# BIT_6.net
KiCad netlist of a schematic drawn in EasyEDA
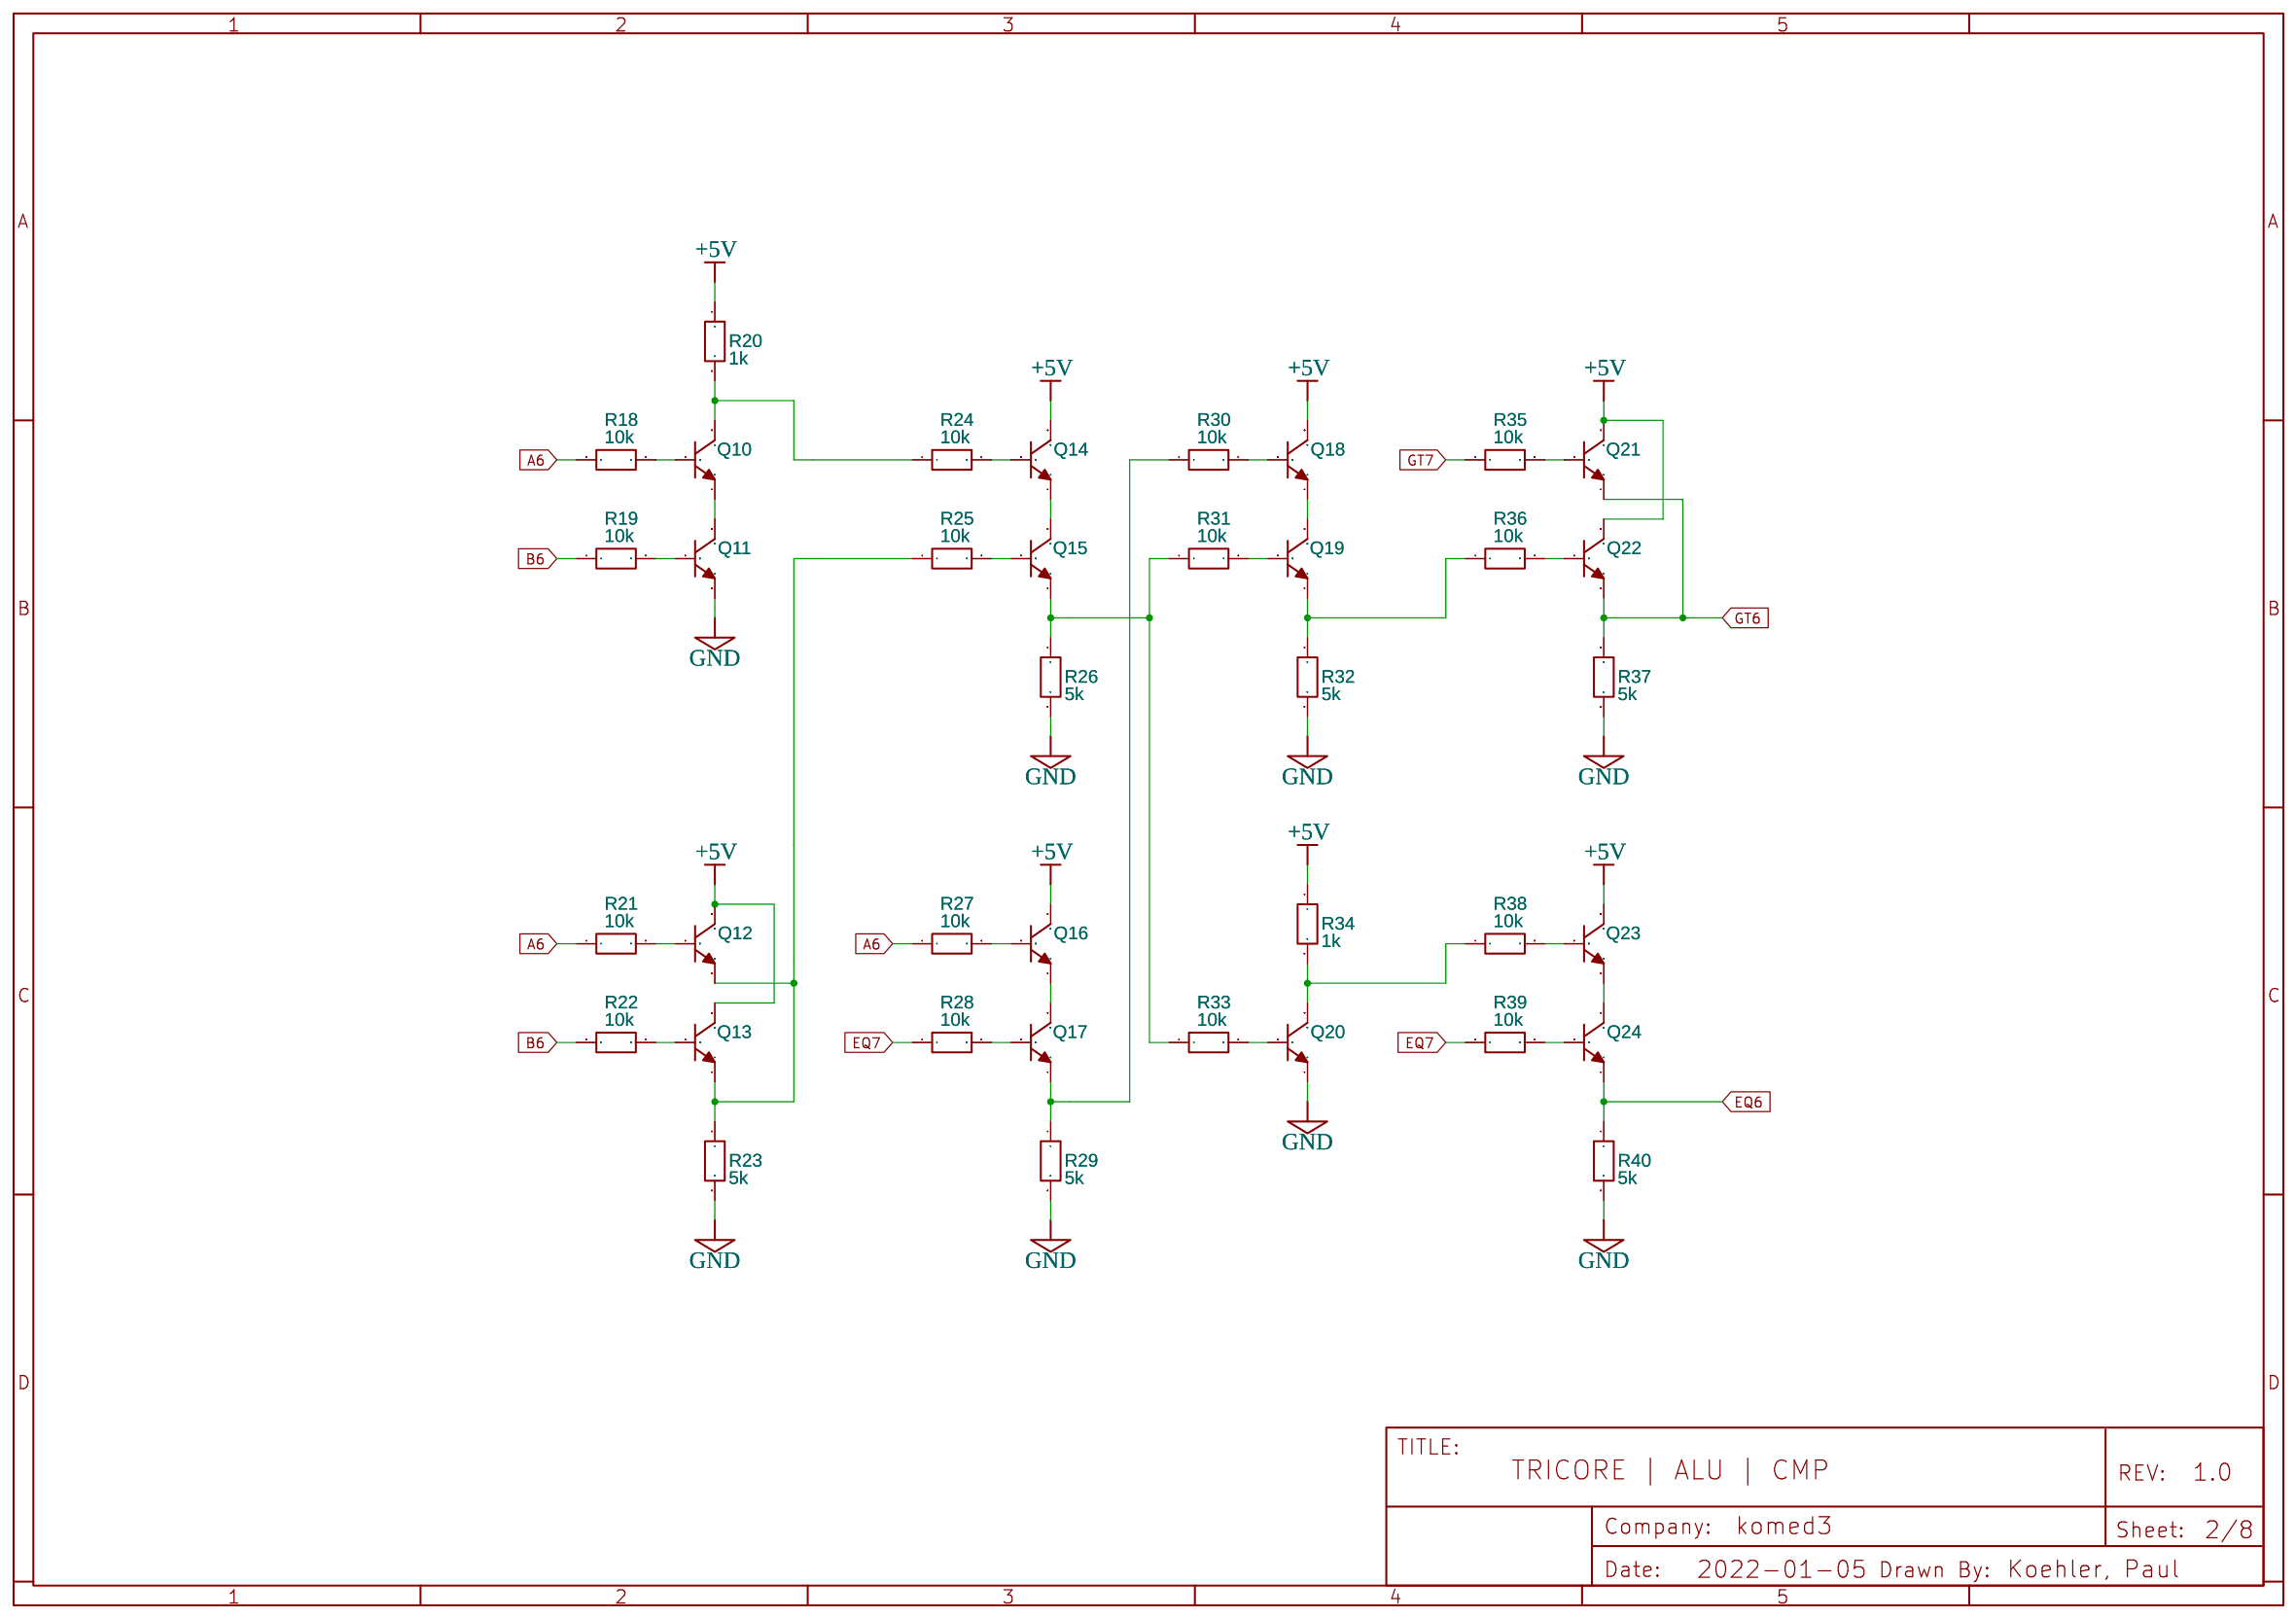
[diagram p0: schematic sheet]

(export (version "E")
  (design (tool "Eeschema 10.0.6"))
  (components
    (comp (ref "Q10")
      (value "2N3904(TO-92)")
      (fields (field (name "BOM_Manufacturer Part") "2N3904") (field (name "BOM_Supplier Part") "C118538"))
      (libsource (lib "") (part "2N3904(TO-92)"))
    )
    (comp (ref "Q11")
      (value "2N3904(TO-92)")
      (fields (field (name "BOM_Manufacturer Part") "2N3904") (field (name "BOM_Supplier Part") "C118538"))
      (libsource (lib "") (part "2N3904(TO-92)"))
    )
    (comp (ref "Q12")
      (value "2N3904(TO-92)")
      (fields (field (name "BOM_Manufacturer Part") "2N3904") (field (name "BOM_Supplier Part") "C118538"))
      (libsource (lib "") (part "2N3904(TO-92)"))
    )
    (comp (ref "Q13")
      (value "2N3904(TO-92)")
      (fields (field (name "BOM_Manufacturer Part") "2N3904") (field (name "BOM_Supplier Part") "C118538"))
      (libsource (lib "") (part "2N3904(TO-92)"))
    )
    (comp (ref "Q14")
      (value "2N3904(TO-92)")
      (fields (field (name "BOM_Manufacturer Part") "2N3904") (field (name "BOM_Supplier Part") "C118538"))
      (libsource (lib "") (part "2N3904(TO-92)"))
    )
    (comp (ref "Q15")
      (value "2N3904(TO-92)")
      (fields (field (name "BOM_Manufacturer Part") "2N3904") (field (name "BOM_Supplier Part") "C118538"))
      (libsource (lib "") (part "2N3904(TO-92)"))
    )
    (comp (ref "Q16")
      (value "2N3904(TO-92)")
      (fields (field (name "BOM_Manufacturer Part") "2N3904") (field (name "BOM_Supplier Part") "C118538"))
      (libsource (lib "") (part "2N3904(TO-92)"))
    )
    (comp (ref "Q17")
      (value "2N3904(TO-92)")
      (fields (field (name "BOM_Manufacturer Part") "2N3904") (field (name "BOM_Supplier Part") "C118538"))
      (libsource (lib "") (part "2N3904(TO-92)"))
    )
    (comp (ref "Q18")
      (value "2N3904(TO-92)")
      (fields (field (name "BOM_Manufacturer Part") "2N3904") (field (name "BOM_Supplier Part") "C118538"))
      (libsource (lib "") (part "2N3904(TO-92)"))
    )
    (comp (ref "Q19")
      (value "2N3904(TO-92)")
      (fields (field (name "BOM_Manufacturer Part") "2N3904") (field (name "BOM_Supplier Part") "C118538"))
      (libsource (lib "") (part "2N3904(TO-92)"))
    )
    (comp (ref "Q20")
      (value "2N3904(TO-92)")
      (fields (field (name "BOM_Manufacturer Part") "2N3904") (field (name "BOM_Supplier Part") "C118538"))
      (libsource (lib "") (part "2N3904(TO-92)"))
    )
    (comp (ref "Q21")
      (value "2N3904(TO-92)")
      (fields (field (name "BOM_Manufacturer Part") "2N3904") (field (name "BOM_Supplier Part") "C118538"))
      (libsource (lib "") (part "2N3904(TO-92)"))
    )
    (comp (ref "Q22")
      (value "2N3904(TO-92)")
      (fields (field (name "BOM_Manufacturer Part") "2N3904") (field (name "BOM_Supplier Part") "C118538"))
      (libsource (lib "") (part "2N3904(TO-92)"))
    )
    (comp (ref "Q23")
      (value "2N3904(TO-92)")
      (fields (field (name "BOM_Manufacturer Part") "2N3904") (field (name "BOM_Supplier Part") "C118538"))
      (libsource (lib "") (part "2N3904(TO-92)"))
    )
    (comp (ref "Q24")
      (value "2N3904(TO-92)")
      (fields (field (name "BOM_Manufacturer Part") "2N3904") (field (name "BOM_Supplier Part") "C118538"))
      (libsource (lib "") (part "2N3904(TO-92)"))
    )
    (comp (ref "R18") (value "10k") (libsource (lib "") (part "R_AXIAL-0.3_EU")))
    (comp (ref "R19") (value "10k") (libsource (lib "") (part "R_AXIAL-0.3_EU")))
    (comp (ref "R20") (value "1k") (libsource (lib "") (part "R_AXIAL-0.3_EU_1")))
    (comp (ref "R21") (value "10k") (libsource (lib "") (part "R_AXIAL-0.3_EU")))
    (comp (ref "R22") (value "10k") (libsource (lib "") (part "R_AXIAL-0.3_EU")))
    (comp (ref "R23") (value "5k") (libsource (lib "") (part "R_AXIAL-0.3_EU_1")))
    (comp (ref "R24") (value "10k") (libsource (lib "") (part "R_AXIAL-0.3_EU")))
    (comp (ref "R25") (value "10k") (libsource (lib "") (part "R_AXIAL-0.3_EU")))
    (comp (ref "R26") (value "5k") (libsource (lib "") (part "R_AXIAL-0.3_EU_1")))
    (comp (ref "R27") (value "10k") (libsource (lib "") (part "R_AXIAL-0.3_EU")))
    (comp (ref "R28") (value "10k") (libsource (lib "") (part "R_AXIAL-0.3_EU")))
    (comp (ref "R29") (value "5k") (libsource (lib "") (part "R_AXIAL-0.3_EU_1")))
    (comp (ref "R30") (value "10k") (libsource (lib "") (part "R_AXIAL-0.3_EU")))
    (comp (ref "R31") (value "10k") (libsource (lib "") (part "R_AXIAL-0.3_EU")))
    (comp (ref "R32") (value "5k") (libsource (lib "") (part "R_AXIAL-0.3_EU_1")))
    (comp (ref "R33") (value "10k") (libsource (lib "") (part "R_AXIAL-0.3_EU")))
    (comp (ref "R34") (value "1k") (libsource (lib "") (part "R_AXIAL-0.3_EU_1")))
    (comp (ref "R35") (value "10k") (libsource (lib "") (part "R_AXIAL-0.3_EU")))
    (comp (ref "R36") (value "10k") (libsource (lib "") (part "R_AXIAL-0.3_EU")))
    (comp (ref "R37") (value "5k") (libsource (lib "") (part "R_AXIAL-0.3_EU_1")))
    (comp (ref "R38") (value "10k") (libsource (lib "") (part "R_AXIAL-0.3_EU")))
    (comp (ref "R39") (value "10k") (libsource (lib "") (part "R_AXIAL-0.3_EU")))
    (comp (ref "R40") (value "5k") (libsource (lib "") (part "R_AXIAL-0.3_EU_1")))
  )
  (nets
    (net (code "1") (name "+5V") (class "Default")
      (node (ref "Q12") (pin "3") (pinfunction "C_3") (pintype "unspecified"))
      (node (ref "Q13") (pin "3") (pinfunction "C_3") (pintype "unspecified"))
      (node (ref "Q14") (pin "3") (pinfunction "C_3") (pintype "unspecified"))
      (node (ref "Q16") (pin "3") (pinfunction "C_3") (pintype "unspecified"))
      (node (ref "Q18") (pin "3") (pinfunction "C_3") (pintype "unspecified"))
      (node (ref "Q21") (pin "3") (pinfunction "C_3") (pintype "unspecified"))
      (node (ref "Q22") (pin "3") (pinfunction "C_3") (pintype "unspecified"))
      (node (ref "Q23") (pin "3") (pinfunction "C_3") (pintype "unspecified"))
      (node (ref "R20") (pin "1") (pinfunction "1_1") (pintype "unspecified"))
      (node (ref "R34") (pin "1") (pinfunction "1_1") (pintype "unspecified"))
    )
    (net (code "2") (name "A6") (class "Default")
      (node (ref "R18") (pin "1") (pinfunction "1_1") (pintype "unspecified"))
      (node (ref "R21") (pin "1") (pinfunction "1_1") (pintype "unspecified"))
      (node (ref "R27") (pin "1") (pinfunction "1_1") (pintype "unspecified"))
    )
    (net (code "3") (name "B6") (class "Default")
      (node (ref "R19") (pin "1") (pinfunction "1_1") (pintype "unspecified"))
      (node (ref "R22") (pin "1") (pinfunction "1_1") (pintype "unspecified"))
    )
    (net (code "4") (name "EQ6") (class "Default")
      (node (ref "Q24") (pin "1") (pinfunction "E_1") (pintype "unspecified"))
      (node (ref "R40") (pin "1") (pinfunction "1_1") (pintype "unspecified"))
    )
    (net (code "5") (name "EQ7") (class "Default")
      (node (ref "R28") (pin "1") (pinfunction "1_1") (pintype "unspecified"))
      (node (ref "R39") (pin "1") (pinfunction "1_1") (pintype "unspecified"))
    )
    (net (code "6") (name "GND") (class "Default")
      (node (ref "Q11") (pin "1") (pinfunction "E_1") (pintype "unspecified"))
      (node (ref "Q20") (pin "1") (pinfunction "E_1") (pintype "unspecified"))
      (node (ref "R23") (pin "2") (pinfunction "2_2") (pintype "unspecified"))
      (node (ref "R26") (pin "2") (pinfunction "2_2") (pintype "unspecified"))
      (node (ref "R29") (pin "2") (pinfunction "2_2") (pintype "unspecified"))
      (node (ref "R32") (pin "2") (pinfunction "2_2") (pintype "unspecified"))
      (node (ref "R37") (pin "2") (pinfunction "2_2") (pintype "unspecified"))
      (node (ref "R40") (pin "2") (pinfunction "2_2") (pintype "unspecified"))
    )
    (net (code "7") (name "GT6") (class "Default")
      (node (ref "Q21") (pin "1") (pinfunction "E_1") (pintype "unspecified"))
      (node (ref "Q22") (pin "1") (pinfunction "E_1") (pintype "unspecified"))
      (node (ref "R37") (pin "1") (pinfunction "1_1") (pintype "unspecified"))
    )
    (net (code "8") (name "GT7") (class "Default")
      (node (ref "R35") (pin "1") (pinfunction "1_1") (pintype "unspecified"))
    )
    (net (code "9") (name "Net-(Q10-B)") (class "Default")
      (node (ref "Q10") (pin "2") (pinfunction "B_2") (pintype "unspecified"))
      (node (ref "R18") (pin "2") (pinfunction "2_2") (pintype "unspecified"))
    )
    (net (code "10") (name "Net-(Q10-C)") (class "Default")
      (node (ref "Q10") (pin "3") (pinfunction "C_3") (pintype "unspecified"))
      (node (ref "R20") (pin "2") (pinfunction "2_2") (pintype "unspecified"))
      (node (ref "R24") (pin "1") (pinfunction "1_1") (pintype "unspecified"))
    )
    (net (code "11") (name "Net-(Q10-E)") (class "Default")
      (node (ref "Q10") (pin "1") (pinfunction "E_1") (pintype "unspecified"))
      (node (ref "Q11") (pin "3") (pinfunction "C_3") (pintype "unspecified"))
    )
    (net (code "12") (name "Net-(Q11-B)") (class "Default")
      (node (ref "Q11") (pin "2") (pinfunction "B_2") (pintype "unspecified"))
      (node (ref "R19") (pin "2") (pinfunction "2_2") (pintype "unspecified"))
    )
    (net (code "13") (name "Net-(Q12-B)") (class "Default")
      (node (ref "Q12") (pin "2") (pinfunction "B_2") (pintype "unspecified"))
      (node (ref "R21") (pin "2") (pinfunction "2_2") (pintype "unspecified"))
    )
    (net (code "14") (name "Net-(Q12-E)") (class "Default")
      (node (ref "Q12") (pin "1") (pinfunction "E_1") (pintype "unspecified"))
      (node (ref "Q13") (pin "1") (pinfunction "E_1") (pintype "unspecified"))
      (node (ref "R23") (pin "1") (pinfunction "1_1") (pintype "unspecified"))
      (node (ref "R25") (pin "1") (pinfunction "1_1") (pintype "unspecified"))
    )
    (net (code "15") (name "Net-(Q13-B)") (class "Default")
      (node (ref "Q13") (pin "2") (pinfunction "B_2") (pintype "unspecified"))
      (node (ref "R22") (pin "2") (pinfunction "2_2") (pintype "unspecified"))
    )
    (net (code "16") (name "Net-(Q14-B)") (class "Default")
      (node (ref "Q14") (pin "2") (pinfunction "B_2") (pintype "unspecified"))
      (node (ref "R24") (pin "2") (pinfunction "2_2") (pintype "unspecified"))
    )
    (net (code "17") (name "Net-(Q14-E)") (class "Default")
      (node (ref "Q14") (pin "1") (pinfunction "E_1") (pintype "unspecified"))
      (node (ref "Q15") (pin "3") (pinfunction "C_3") (pintype "unspecified"))
    )
    (net (code "18") (name "Net-(Q15-B)") (class "Default")
      (node (ref "Q15") (pin "2") (pinfunction "B_2") (pintype "unspecified"))
      (node (ref "R25") (pin "2") (pinfunction "2_2") (pintype "unspecified"))
    )
    (net (code "19") (name "Net-(Q15-E)") (class "Default")
      (node (ref "Q15") (pin "1") (pinfunction "E_1") (pintype "unspecified"))
      (node (ref "R26") (pin "1") (pinfunction "1_1") (pintype "unspecified"))
      (node (ref "R31") (pin "1") (pinfunction "1_1") (pintype "unspecified"))
      (node (ref "R33") (pin "1") (pinfunction "1_1") (pintype "unspecified"))
    )
    (net (code "20") (name "Net-(Q16-B)") (class "Default")
      (node (ref "Q16") (pin "2") (pinfunction "B_2") (pintype "unspecified"))
      (node (ref "R27") (pin "2") (pinfunction "2_2") (pintype "unspecified"))
    )
    (net (code "21") (name "Net-(Q16-E)") (class "Default")
      (node (ref "Q16") (pin "1") (pinfunction "E_1") (pintype "unspecified"))
      (node (ref "Q17") (pin "3") (pinfunction "C_3") (pintype "unspecified"))
    )
    (net (code "22") (name "Net-(Q17-B)") (class "Default")
      (node (ref "Q17") (pin "2") (pinfunction "B_2") (pintype "unspecified"))
      (node (ref "R28") (pin "2") (pinfunction "2_2") (pintype "unspecified"))
    )
    (net (code "23") (name "Net-(Q17-E)") (class "Default")
      (node (ref "Q17") (pin "1") (pinfunction "E_1") (pintype "unspecified"))
      (node (ref "R29") (pin "1") (pinfunction "1_1") (pintype "unspecified"))
      (node (ref "R30") (pin "1") (pinfunction "1_1") (pintype "unspecified"))
    )
    (net (code "24") (name "Net-(Q18-B)") (class "Default")
      (node (ref "Q18") (pin "2") (pinfunction "B_2") (pintype "unspecified"))
      (node (ref "R30") (pin "2") (pinfunction "2_2") (pintype "unspecified"))
    )
    (net (code "25") (name "Net-(Q18-E)") (class "Default")
      (node (ref "Q18") (pin "1") (pinfunction "E_1") (pintype "unspecified"))
      (node (ref "Q19") (pin "3") (pinfunction "C_3") (pintype "unspecified"))
    )
    (net (code "26") (name "Net-(Q19-B)") (class "Default")
      (node (ref "Q19") (pin "2") (pinfunction "B_2") (pintype "unspecified"))
      (node (ref "R31") (pin "2") (pinfunction "2_2") (pintype "unspecified"))
    )
    (net (code "27") (name "Net-(Q19-E)") (class "Default")
      (node (ref "Q19") (pin "1") (pinfunction "E_1") (pintype "unspecified"))
      (node (ref "R32") (pin "1") (pinfunction "1_1") (pintype "unspecified"))
      (node (ref "R36") (pin "1") (pinfunction "1_1") (pintype "unspecified"))
    )
    (net (code "28") (name "Net-(Q20-B)") (class "Default")
      (node (ref "Q20") (pin "2") (pinfunction "B_2") (pintype "unspecified"))
      (node (ref "R33") (pin "2") (pinfunction "2_2") (pintype "unspecified"))
    )
    (net (code "29") (name "Net-(Q20-C)") (class "Default")
      (node (ref "Q20") (pin "3") (pinfunction "C_3") (pintype "unspecified"))
      (node (ref "R34") (pin "2") (pinfunction "2_2") (pintype "unspecified"))
      (node (ref "R38") (pin "1") (pinfunction "1_1") (pintype "unspecified"))
    )
    (net (code "30") (name "Net-(Q21-B)") (class "Default")
      (node (ref "Q21") (pin "2") (pinfunction "B_2") (pintype "unspecified"))
      (node (ref "R35") (pin "2") (pinfunction "2_2") (pintype "unspecified"))
    )
    (net (code "31") (name "Net-(Q22-B)") (class "Default")
      (node (ref "Q22") (pin "2") (pinfunction "B_2") (pintype "unspecified"))
      (node (ref "R36") (pin "2") (pinfunction "2_2") (pintype "unspecified"))
    )
    (net (code "32") (name "Net-(Q23-B)") (class "Default")
      (node (ref "Q23") (pin "2") (pinfunction "B_2") (pintype "unspecified"))
      (node (ref "R38") (pin "2") (pinfunction "2_2") (pintype "unspecified"))
    )
    (net (code "33") (name "Net-(Q23-E)") (class "Default")
      (node (ref "Q23") (pin "1") (pinfunction "E_1") (pintype "unspecified"))
      (node (ref "Q24") (pin "3") (pinfunction "C_3") (pintype "unspecified"))
    )
    (net (code "34") (name "Net-(Q24-B)") (class "Default")
      (node (ref "Q24") (pin "2") (pinfunction "B_2") (pintype "unspecified"))
      (node (ref "R39") (pin "2") (pinfunction "2_2") (pintype "unspecified"))
    )
  )
)
